# esp07_co2.net
KiCad netlist of a schematic drawn in EAGLE
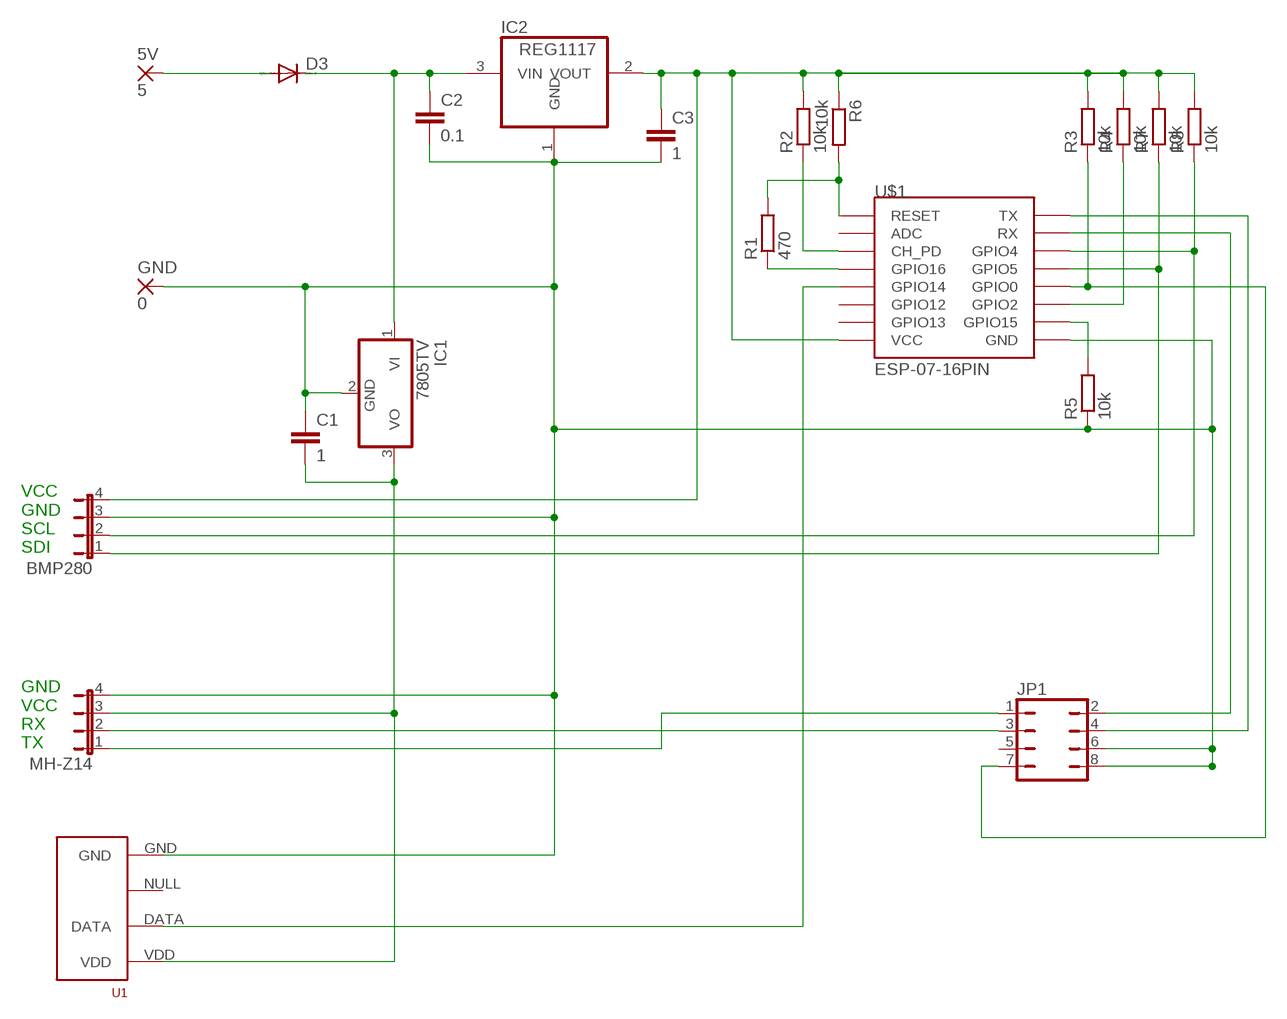
[diagram p0: schematic, sheet 1]

(export (version "E")
  (design (tool "Eeschema 10.0.6"))
  (components
    (comp (ref "5V")
      (value "5")
      (footprint "eagle-import:2,54_0,9")
      (libsource (lib "eagle-import") (part "2,54/0,9"))
    )
    (comp (ref "BMP280")
      (value "JP4E")
      (footprint "eagle-import:JP4")
      (libsource (lib "eagle-import") (part "JP4E"))
    )
    (comp (ref "C1")
      (value "1")
      (footprint "eagle-import:C0805")
      (libsource (lib "eagle-import") (part "C-EUC0805"))
    )
    (comp (ref "C2")
      (value "0.1")
      (footprint "eagle-import:C0805")
      (libsource (lib "eagle-import") (part "C-EUC0805"))
    )
    (comp (ref "C3")
      (value "1")
      (footprint "eagle-import:C0805")
      (libsource (lib "eagle-import") (part "C-EUC0805"))
    )
    (comp (ref "D3")
      (value "DIODE-SOD80C")
      (footprint "eagle-import:SOD80C")
      (libsource (lib "eagle-import") (part "DIODE-SOD80C"))
    )
    (comp (ref "GND")
      (value "0")
      (footprint "eagle-import:2,54_0,9")
      (libsource (lib "eagle-import") (part "2,54/0,9"))
    )
    (comp (ref "IC1")
      (value "7805TV")
      (footprint "eagle-import:TO220V")
      (libsource (lib "eagle-import") (part "78TV05"))
    )
    (comp (ref "IC2")
      (value "REG1117")
      (footprint "eagle-import:SOT223")
      (libsource (lib "eagle-import") (part "REG1117"))
    )
    (comp (ref "JP1")
      (value "JP4Q")
      (footprint "eagle-import:JP4Q")
      (libsource (lib "eagle-import") (part "JP4Q"))
    )
    (comp (ref "MH-Z14")
      (value "JP4E")
      (footprint "eagle-import:JP4")
      (libsource (lib "eagle-import") (part "JP4E"))
    )
    (comp (ref "R1")
      (value "470")
      (footprint "eagle-import:R1206")
      (libsource (lib "eagle-import") (part "R-EU_R1206"))
    )
    (comp (ref "R2")
      (value "10k")
      (footprint "eagle-import:R1206")
      (libsource (lib "eagle-import") (part "R-EU_R1206"))
    )
    (comp (ref "R3")
      (value "10k")
      (footprint "eagle-import:R1206")
      (libsource (lib "eagle-import") (part "R-EU_R1206"))
    )
    (comp (ref "R4")
      (value "10k")
      (footprint "eagle-import:R1206")
      (libsource (lib "eagle-import") (part "R-EU_R1206"))
    )
    (comp (ref "R5")
      (value "10k")
      (footprint "eagle-import:R1206")
      (libsource (lib "eagle-import") (part "R-EU_R1206"))
    )
    (comp (ref "R6")
      (value "10k")
      (footprint "eagle-import:R1206")
      (libsource (lib "eagle-import") (part "R-EU_R1206"))
    )
    (comp (ref "R7")
      (value "10k")
      (footprint "eagle-import:R1206")
      (libsource (lib "eagle-import") (part "R-EU_R1206"))
    )
    (comp (ref "R8")
      (value "10k")
      (footprint "eagle-import:R1206")
      (libsource (lib "eagle-import") (part "R-EU_R1206"))
    )
    (comp (ref "U$1")
      (value "ESP-07-16PIN")
      (footprint "eagle-import:ESP-07-16PIN")
      (libsource (lib "eagle-import") (part "ESP-07-16PIN"))
    )
    (comp (ref "U1")
      (value "RHT03_DHT-22_AM2302RA")
      (footprint "eagle-import:RHT03_DHT-22_RA")
      (libsource (lib "eagle-import") (part "RHT03_DHT-22_AM2302RA"))
    )
  )
  (nets
    (net (code "1") (name "Net-(5V-P)") (class "Default")
      (node (ref "5V") (pin "1") (pinfunction "P_1") (pintype "passive"))
      (node (ref "D3") (pin "A") (pinfunction "A_A") (pintype "passive"))
    )
    (net (code "2") (name "Net-(BMP280-Pad1)") (class "Default")
      (node (ref "BMP280") (pin "1") (pinfunction "1_1") (pintype "passive"))
      (node (ref "R7") (pin "1") (pinfunction "1_1") (pintype "passive"))
      (node (ref "U$1") (pin "GPIO5") (pinfunction "GPIO5_GPIO5") (pintype "bidirectional"))
    )
    (net (code "3") (name "Net-(BMP280-Pad2)") (class "Default")
      (node (ref "BMP280") (pin "2") (pinfunction "2_2") (pintype "passive"))
      (node (ref "R8") (pin "1") (pinfunction "1_1") (pintype "passive"))
      (node (ref "U$1") (pin "GPIO4") (pinfunction "GPIO4_GPIO4") (pintype "bidirectional"))
    )
    (net (code "4") (name "Net-(GND-P)") (class "Default")
      (node (ref "BMP280") (pin "3") (pinfunction "3_3") (pintype "passive"))
      (node (ref "C1") (pin "1") (pinfunction "1_1") (pintype "passive"))
      (node (ref "C2") (pin "2") (pinfunction "2_2") (pintype "passive"))
      (node (ref "C3") (pin "2") (pinfunction "2_2") (pintype "passive"))
      (node (ref "GND") (pin "1") (pinfunction "P_1") (pintype "passive"))
      (node (ref "IC1") (pin "2") (pinfunction "GND_2") (pintype "passive"))
      (node (ref "IC2") (pin "1") (pinfunction "GND_1") (pintype "power_in"))
      (node (ref "JP1") (pin "6") (pinfunction "6_6") (pintype "passive"))
      (node (ref "JP1") (pin "8") (pinfunction "8_8") (pintype "passive"))
      (node (ref "MH-Z14") (pin "4") (pinfunction "4_4") (pintype "passive"))
      (node (ref "R5") (pin "1") (pinfunction "1_1") (pintype "passive"))
      (node (ref "U$1") (pin "GND") (pinfunction "GND_GND") (pintype "bidirectional"))
      (node (ref "U1") (pin "GND") (pinfunction "GND_GND") (pintype "power_in"))
    )
    (net (code "5") (name "Net-(IC1-VI)") (class "Default")
      (node (ref "C2") (pin "1") (pinfunction "1_1") (pintype "passive"))
      (node (ref "D3") (pin "C") (pinfunction "C_C") (pintype "passive"))
      (node (ref "IC1") (pin "1") (pinfunction "VI_1") (pintype "input"))
      (node (ref "IC2") (pin "3") (pinfunction "VIN_3") (pintype "input"))
    )
    (net (code "6") (name "Net-(IC1-VO)") (class "Default")
      (node (ref "C1") (pin "2") (pinfunction "2_2") (pintype "passive"))
      (node (ref "IC1") (pin "3") (pinfunction "VO_3") (pintype "passive"))
      (node (ref "MH-Z14") (pin "3") (pinfunction "3_3") (pintype "passive"))
      (node (ref "U1") (pin "VDD") (pinfunction "VDD_VDD") (pintype "power_in"))
    )
    (net (code "7") (name "Net-(IC2-VOUT)") (class "Default")
      (node (ref "BMP280") (pin "4") (pinfunction "4_4") (pintype "passive"))
      (node (ref "C3") (pin "1") (pinfunction "1_1") (pintype "passive"))
      (node (ref "IC2") (pin "2") (pinfunction "VOUT_2") (pintype "output"))
      (node (ref "R2") (pin "2") (pinfunction "2_2") (pintype "passive"))
      (node (ref "R3") (pin "2") (pinfunction "2_2") (pintype "passive"))
      (node (ref "R4") (pin "2") (pinfunction "2_2") (pintype "passive"))
      (node (ref "R6") (pin "1") (pinfunction "1_1") (pintype "passive"))
      (node (ref "R7") (pin "2") (pinfunction "2_2") (pintype "passive"))
      (node (ref "R8") (pin "2") (pinfunction "2_2") (pintype "passive"))
      (node (ref "U$1") (pin "VCC") (pinfunction "VCC_VCC") (pintype "bidirectional"))
    )
    (net (code "8") (name "Net-(JP1-Pad1)") (class "Default")
      (node (ref "JP1") (pin "1") (pinfunction "1_1") (pintype "passive"))
      (node (ref "MH-Z14") (pin "1") (pinfunction "1_1") (pintype "passive"))
    )
    (net (code "9") (name "Net-(JP1-Pad2)") (class "Default")
      (node (ref "JP1") (pin "2") (pinfunction "2_2") (pintype "passive"))
      (node (ref "U$1") (pin "RX") (pinfunction "RX_RX") (pintype "bidirectional"))
    )
    (net (code "10") (name "Net-(JP1-Pad3)") (class "Default")
      (node (ref "JP1") (pin "3") (pinfunction "3_3") (pintype "passive"))
      (node (ref "MH-Z14") (pin "2") (pinfunction "2_2") (pintype "passive"))
    )
    (net (code "11") (name "Net-(JP1-Pad4)") (class "Default")
      (node (ref "JP1") (pin "4") (pinfunction "4_4") (pintype "passive"))
      (node (ref "U$1") (pin "TX") (pinfunction "TX_TX") (pintype "bidirectional"))
    )
    (net (code "12") (name "Net-(JP1-Pad7)") (class "Default")
      (node (ref "JP1") (pin "7") (pinfunction "7_7") (pintype "passive"))
      (node (ref "R3") (pin "1") (pinfunction "1_1") (pintype "passive"))
      (node (ref "U$1") (pin "GPIO0") (pinfunction "GPIO0_GPIO0") (pintype "bidirectional"))
    )
    (net (code "13") (name "Net-(R1-Pad1)") (class "Default")
      (node (ref "R1") (pin "1") (pinfunction "1_1") (pintype "passive"))
      (node (ref "U$1") (pin "GPIO16") (pinfunction "GPIO16_GPIO16") (pintype "bidirectional"))
    )
    (net (code "14") (name "Net-(R2-Pad1)") (class "Default")
      (node (ref "R2") (pin "1") (pinfunction "1_1") (pintype "passive"))
      (node (ref "U$1") (pin "CH_PD") (pinfunction "CH_PD_CH_PD") (pintype "bidirectional"))
    )
    (net (code "15") (name "Net-(R4-Pad1)") (class "Default")
      (node (ref "R4") (pin "1") (pinfunction "1_1") (pintype "passive"))
      (node (ref "U$1") (pin "GPIO2") (pinfunction "GPIO2_GPIO2") (pintype "bidirectional"))
    )
    (net (code "16") (name "Net-(R5-Pad2)") (class "Default")
      (node (ref "R5") (pin "2") (pinfunction "2_2") (pintype "passive"))
      (node (ref "U$1") (pin "GPIO15") (pinfunction "GPIO15_GPIO15") (pintype "bidirectional"))
    )
    (net (code "17") (name "Net-(U$1-PadGPIO14)") (class "Default")
      (node (ref "U$1") (pin "GPIO14") (pinfunction "GPIO14_GPIO14") (pintype "bidirectional"))
      (node (ref "U1") (pin "DATA") (pinfunction "DATA_DATA") (pintype "bidirectional"))
    )
    (net (code "18") (name "Net-(U$1-RESET)") (class "Default")
      (node (ref "R1") (pin "2") (pinfunction "2_2") (pintype "passive"))
      (node (ref "R6") (pin "2") (pinfunction "2_2") (pintype "passive"))
      (node (ref "U$1") (pin "REST") (pinfunction "RESET_REST") (pintype "bidirectional"))
    )
    (net (code "19") (name "unconnected-(JP1-Pad5)") (class "Default")
      (node (ref "JP1") (pin "5") (pinfunction "5_5") (pintype "passive"))
    )
    (net (code "20") (name "unconnected-(U$1-PadADC)") (class "Default")
      (node (ref "U$1") (pin "ADC") (pinfunction "ADC_ADC") (pintype "bidirectional"))
    )
    (net (code "21") (name "unconnected-(U$1-PadGPIO12)") (class "Default")
      (node (ref "U$1") (pin "GPIO12") (pinfunction "GPIO12_GPIO12") (pintype "bidirectional"))
    )
    (net (code "22") (name "unconnected-(U$1-PadGPIO13)") (class "Default")
      (node (ref "U$1") (pin "GPIO13") (pinfunction "GPIO13_GPIO13") (pintype "bidirectional"))
    )
    (net (code "23") (name "unconnected-(U1-PadNULL)") (class "Default")
      (node (ref "U1") (pin "NULL") (pinfunction "NULL_NULL") (pintype "no_connect"))
    )
  )
)
